# mcu_atmega.net
KiCad netlist of a schematic drawn in Altium Designer
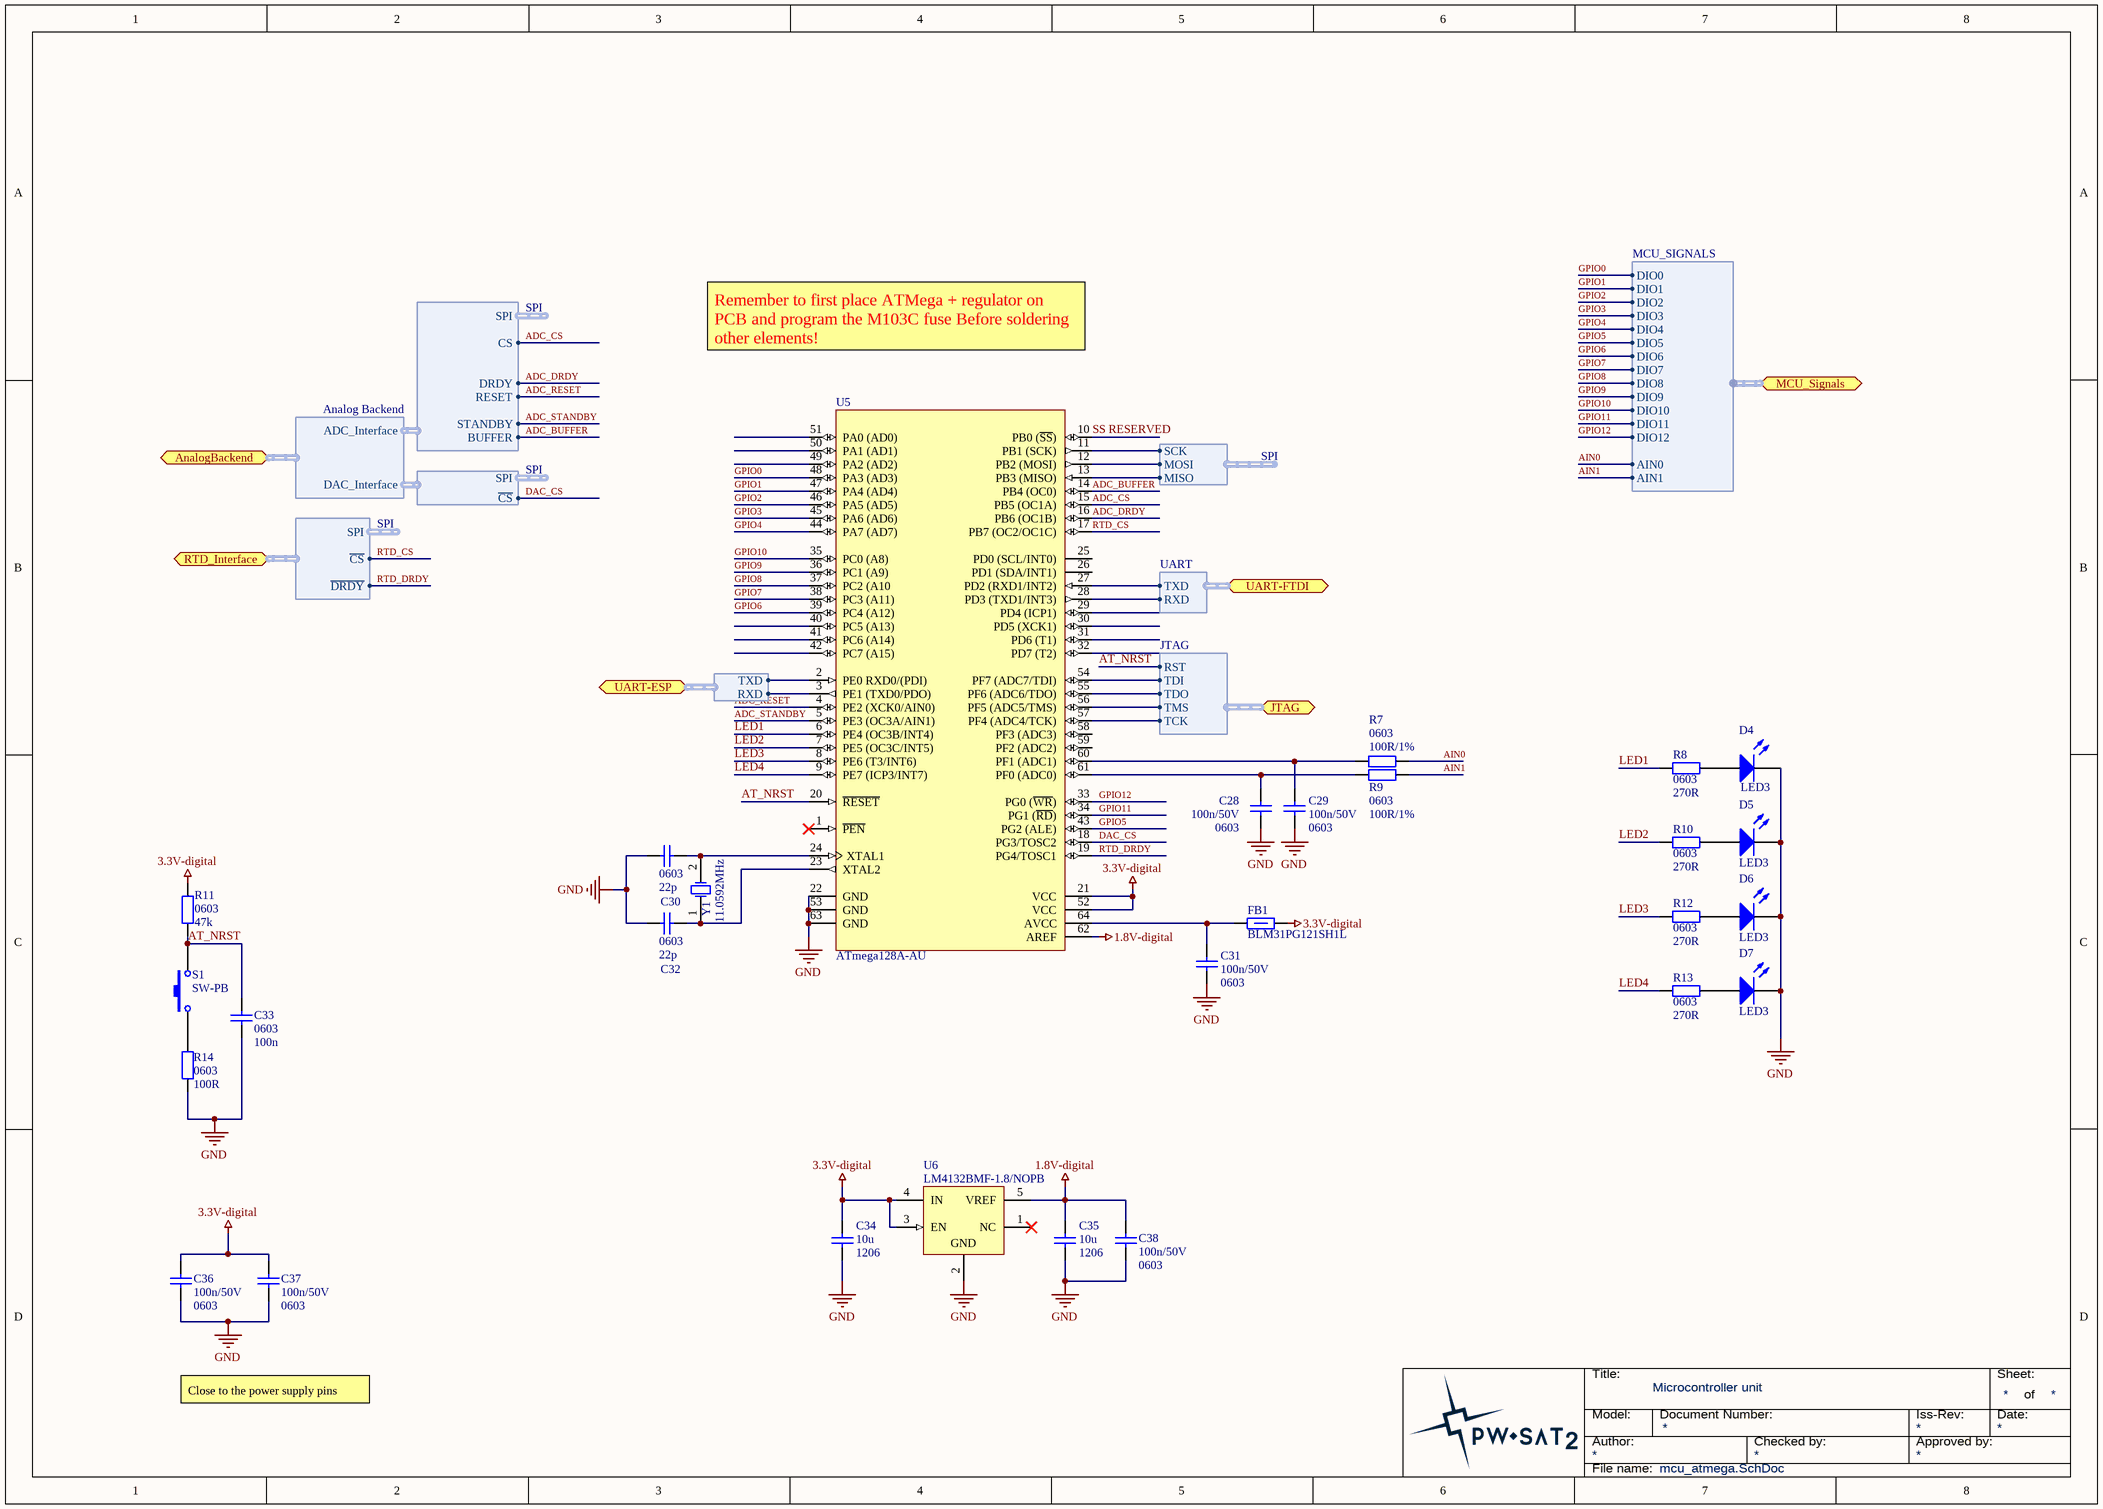
[diagram p0: mcu_atmega.SchDoc]

(export (version "E")
  (design (tool "Eeschema 10.0.6"))
  (components
    (comp (ref "C28")
      (value "100n/50V")
      (footprint "SMD_Capacitor_0603")
      (description "Ceramic Cap Kemet COTS 100n/50V X7R 0603")
      (fields
        (field (name "MANUFACTURER") "Kemet")
        (field (name "MANUFACTURERPARTNUMBER") "C0603T104K5RALTU")
        (field (name "PACKAGE") "0603")
      )
      (libsource (lib "capacitors") (part "Cer_C0603T104K5RALTU"))
    )
    (comp (ref "C29")
      (value "100n/50V")
      (footprint "SMD_Capacitor_0603")
      (description "Ceramic Cap Kemet COTS 100n/50V X7R 0603")
      (fields
        (field (name "MANUFACTURER") "Kemet")
        (field (name "MANUFACTURERPARTNUMBER") "C0603T104K5RALTU")
        (field (name "PACKAGE") "0603")
      )
      (libsource (lib "capacitors") (part "Cer_C0603T104K5RALTU"))
    )
    (comp (ref "C30")
      (value "0603")
      (footprint "SMD_Capacitor_0603")
      (description "Capacitor")
      (fields (field (name "ALTIUM_VALUE") "22p") (field (name "PUBLISHER") "Altium Limited"))
      (libsource (lib "Miscellaneous Devices") (part "Cap"))
    )
    (comp (ref "C31")
      (value "100n/50V")
      (footprint "SMD_Capacitor_0603")
      (description "Ceramic Cap Kemet COTS 100n/50V X7R 0603")
      (fields
        (field (name "MANUFACTURER") "Kemet")
        (field (name "MANUFACTURERPARTNUMBER") "C0603T104K5RALTU")
        (field (name "PACKAGE") "0603")
      )
      (libsource (lib "capacitors") (part "Cer_C0603T104K5RALTU"))
    )
    (comp (ref "C32")
      (value "0603")
      (footprint "SMD_Capacitor_0603")
      (description "Capacitor")
      (fields (field (name "ALTIUM_VALUE") "22p") (field (name "PUBLISHER") "Altium Limited"))
      (libsource (lib "Miscellaneous Devices") (part "Cap"))
    )
    (comp (ref "C33")
      (value "0603")
      (footprint "SMD_Capacitor_0603")
      (description "Capacitor")
      (fields (field (name "ALTIUM_VALUE") "100n") (field (name "PUBLISHER") "Altium Limited"))
      (libsource (lib "Miscellaneous Devices") (part "Cap"))
    )
    (comp (ref "C34")
      (value "10u")
      (footprint "SMD_Capacitor_1206")
      (description "Cap")
      (fields (field (name "PACKAGE") "1206"))
      (libsource (lib "capacitors") (part "Cap"))
    )
    (comp (ref "C35")
      (value "10u")
      (footprint "SMD_Capacitor_1206")
      (description "Cap")
      (fields (field (name "PACKAGE") "1206"))
      (libsource (lib "capacitors") (part "Cap"))
    )
    (comp (ref "C36")
      (value "100n/50V")
      (footprint "SMD_Capacitor_0603")
      (description "Ceramic Cap Kemet COTS 100n/50V X7R 0603")
      (fields
        (field (name "MANUFACTURER") "Kemet")
        (field (name "MANUFACTURERPARTNUMBER") "C0603T104K5RALTU")
        (field (name "PACKAGE") "0603")
      )
      (libsource (lib "capacitors") (part "Cer_C0603T104K5RALTU"))
    )
    (comp (ref "C37")
      (value "100n/50V")
      (footprint "SMD_Capacitor_0603")
      (description "Ceramic Cap Kemet COTS 100n/50V X7R 0603")
      (fields
        (field (name "MANUFACTURER") "Kemet")
        (field (name "MANUFACTURERPARTNUMBER") "C0603T104K5RALTU")
        (field (name "PACKAGE") "0603")
      )
      (libsource (lib "capacitors") (part "Cer_C0603T104K5RALTU"))
    )
    (comp (ref "C38")
      (value "100n/50V")
      (footprint "SMD_Capacitor_0603")
      (description "Ceramic Cap Kemet COTS 100n/50V X7R 0603")
      (fields
        (field (name "MANUFACTURER") "Kemet")
        (field (name "MANUFACTURERPARTNUMBER") "C0603T104K5RALTU")
        (field (name "PACKAGE") "0603")
      )
      (libsource (lib "capacitors") (part "Cer_C0603T104K5RALTU"))
    )
    (comp (ref "D4")
      (value "LED3")
      (footprint "LED 0805 Blue")
      (description "Typical BLUE SiC LED")
      (fields (field (name "PUBLISHER") "Altium Limited"))
      (libsource (lib "Miscellaneous Devices") (part "LED3"))
    )
    (comp (ref "D5")
      (value "LED3")
      (footprint "LED 0805 Yellow")
      (description "Typical BLUE SiC LED")
      (fields (field (name "PUBLISHER") "Altium Limited"))
      (libsource (lib "Miscellaneous Devices") (part "LED3"))
    )
    (comp (ref "D6")
      (value "LED3")
      (footprint "LED 0805 GREEN")
      (description "Typical BLUE SiC LED")
      (fields (field (name "PUBLISHER") "Altium Limited"))
      (libsource (lib "Miscellaneous Devices") (part "LED3"))
    )
    (comp (ref "D7")
      (value "LED3")
      (footprint "LED 0805 RED")
      (description "Typical BLUE SiC LED")
      (fields (field (name "PUBLISHER") "Altium Limited"))
      (libsource (lib "Miscellaneous Devices") (part "LED3"))
    )
    (comp (ref "FB1")
      (value "120R/100MHz")
      (footprint "SMD_FerriteBead_1206")
      (description "Ferrite bead, 1206, 0.02HM, 3.5A.")
      (fields (field (name "MANUFACTURER") "Murata") (field (name "MANUFACTURERPARTNUMBER") "BLM31PG121SH1L"))
      (libsource (lib "inductors") (part "BLM31PG121SH1L"))
    )
    (comp (ref "R7")
      (value "100R/1%")
      (footprint "SMD_Resistor_0603")
      (description "100R/1% Vishay CRCW 0603 Resistor. 100mW, 100ppm, 75V.")
      (fields
        (field (name "MANUFACTURER") "Vishay")
        (field (name "MANUFACTURERPARTNUMBER") "CRCW0603100RFKxxxx")
        (field (name "PACKAGE") "0603")
      )
      (libsource (lib "resistors") (part "CRCW0603100RFKxxxx"))
    )
    (comp (ref "R8")
      (value "0603")
      (footprint "SMD_Resistor_0603")
      (description "Resistor")
      (fields (field (name "ALTIUM_VALUE") "270R") (field (name "PUBLISHER") "Altium Limited"))
      (libsource (lib "Miscellaneous Devices") (part "Res2"))
    )
    (comp (ref "R9")
      (value "100R/1%")
      (footprint "SMD_Resistor_0603")
      (description "100R/1% Vishay CRCW 0603 Resistor. 100mW, 100ppm, 75V.")
      (fields
        (field (name "MANUFACTURER") "Vishay")
        (field (name "MANUFACTURERPARTNUMBER") "CRCW0603100RFKxxxx")
        (field (name "PACKAGE") "0603")
      )
      (libsource (lib "") (part "CRCW0603100RFKxxxx_1"))
    )
    (comp (ref "R10")
      (value "0603")
      (footprint "SMD_Resistor_0603")
      (description "Resistor")
      (fields (field (name "ALTIUM_VALUE") "270R") (field (name "PUBLISHER") "Altium Limited"))
      (libsource (lib "Miscellaneous Devices") (part "Res2"))
    )
    (comp (ref "R11")
      (value "0603")
      (footprint "SMD_Resistor_0603")
      (description "Resistor")
      (fields (field (name "ALTIUM_VALUE") "47k") (field (name "PUBLISHER") "Altium Limited"))
      (libsource (lib "") (part "Res2_2"))
    )
    (comp (ref "R12")
      (value "0603")
      (footprint "SMD_Resistor_0603")
      (description "Resistor")
      (fields (field (name "ALTIUM_VALUE") "270R") (field (name "PUBLISHER") "Altium Limited"))
      (libsource (lib "Miscellaneous Devices") (part "Res2"))
    )
    (comp (ref "R13")
      (value "0603")
      (footprint "SMD_Resistor_0603")
      (description "Resistor")
      (fields (field (name "ALTIUM_VALUE") "270R") (field (name "PUBLISHER") "Altium Limited"))
      (libsource (lib "Miscellaneous Devices") (part "Res2"))
    )
    (comp (ref "R14")
      (value "0603")
      (footprint "SMD_Resistor_0603")
      (description "Resistor")
      (fields (field (name "ALTIUM_VALUE") "100R") (field (name "PUBLISHER") "Altium Limited"))
      (libsource (lib "") (part "Res2_1"))
    )
    (comp (ref "S1")
      (value "SW-PB")
      (footprint "Tact Switch 3x6")
      (description "Switch")
      (fields (field (name "PUBLISHER") "Altium Limited"))
      (libsource (lib "Miscellaneous Devices") (part "SW-PB"))
    )
    (comp (ref "U5")
      (value "ATmega128A-AU")
      (footprint "64A_M")
      (libsource (lib "Atmel Microcontroller megaAVR") (part "ATmega128A-AU"))
    )
    (comp (ref "U6")
      (value "LM4132BMF-1.8/NOPB")
      (footprint "MF05A_N")
      (description "Precision Low Dropout Voltage Reference, 5-pin SOT-23, Pb-Free")
      (fields (field (name "MANUFACTURER") "National Semiconductor"))
      (libsource (lib "National Semiconductor Voltage Reference") (part "LM4132BMF-1.8/NOPB"))
    )
    (comp (ref "Y1")
      (value "11.0592MHz")
      (footprint "CRYSTAL_HC49-US-SM")
      (description "LF XTAL003519")
      (fields (field (name "PUBLISHER") "Altium Limited"))
      (libsource (lib "Miscellaneous Devices") (part "XTAL"))
    )
  )
  (nets
    (net (code "11") (name "/ADC_BUFFER") (class "Default")
      (node (ref "U5") (pin "14") (pinfunction "PB4_(OC0)_14") (pintype "bidirectional"))
    )
    (net (code "12") (name "/ADC_CS") (class "Default")
      (node (ref "U5") (pin "15") (pinfunction "PB5_(OC1A)_15") (pintype "bidirectional"))
    )
    (net (code "13") (name "/ADC_DRDY") (class "Default")
      (node (ref "U5") (pin "16") (pinfunction "PB6_(OC1B)_16") (pintype "bidirectional"))
    )
    (net (code "14") (name "/ADC_RESET") (class "Default")
      (node (ref "U5") (pin "4") (pinfunction "PE2_(XCK0/AIN0)_4") (pintype "bidirectional"))
    )
    (net (code "15") (name "/ADC_STANDBY") (class "Default")
      (node (ref "U5") (pin "5") (pinfunction "PE3_(OC3A/AIN1)_5") (pintype "bidirectional"))
    )
    (net (code "16") (name "/AIN0") (class "Default")
      (node (ref "R7") (pin "1") (pinfunction "1_1") (pintype "passive"))
    )
    (net (code "17") (name "/AIN1") (class "Default")
      (node (ref "R9") (pin "2") (pinfunction "2_2") (pintype "passive"))
    )
    (net (code "18") (name "/AT_NRST") (class "Default")
      (node (ref "C33") (pin "2") (pinfunction "2_2") (pintype "passive"))
      (node (ref "R11") (pin "1") (pinfunction "1_1") (pintype "passive"))
      (node (ref "S1") (pin "2") (pinfunction "2_2") (pintype "passive"))
      (node (ref "U5") (pin "20") (pinfunction "~{RESET}_20") (pintype "input"))
    )
    (net (code "19") (name "/DAC_CS") (class "Default")
      (node (ref "U5") (pin "18") (pinfunction "PG3/TOSC2_18") (pintype "bidirectional"))
    )
    (net (code "20") (name "/GPIO0") (class "Default")
      (node (ref "U5") (pin "48") (pinfunction "PA3_(AD3)_48") (pintype "bidirectional"))
    )
    (net (code "21") (name "/GPIO1") (class "Default")
      (node (ref "U5") (pin "47") (pinfunction "PA4_(AD4)_47") (pintype "bidirectional"))
    )
    (net (code "22") (name "/GPIO2") (class "Default")
      (node (ref "U5") (pin "46") (pinfunction "PA5_(AD5)_46") (pintype "bidirectional"))
    )
    (net (code "23") (name "/GPIO3") (class "Default")
      (node (ref "U5") (pin "45") (pinfunction "PA6_(AD6)_45") (pintype "bidirectional"))
    )
    (net (code "24") (name "/GPIO4") (class "Default")
      (node (ref "U5") (pin "44") (pinfunction "PA7_(AD7)_44") (pintype "bidirectional"))
    )
    (net (code "25") (name "/GPIO5") (class "Default")
      (node (ref "U5") (pin "43") (pinfunction "PG2_(ALE)_43") (pintype "bidirectional"))
    )
    (net (code "26") (name "/GPIO6") (class "Default")
      (node (ref "U5") (pin "39") (pinfunction "PC4_(A12)_39") (pintype "bidirectional"))
    )
    (net (code "27") (name "/GPIO7") (class "Default")
      (node (ref "U5") (pin "38") (pinfunction "PC3_(A11)_38") (pintype "bidirectional"))
    )
    (net (code "28") (name "/GPIO8") (class "Default")
      (node (ref "U5") (pin "37") (pinfunction "PC2_(A10_37") (pintype "bidirectional"))
    )
    (net (code "29") (name "/GPIO9") (class "Default")
      (node (ref "U5") (pin "36") (pinfunction "PC1_(A9)_36") (pintype "bidirectional"))
    )
    (net (code "30") (name "/GPIO10") (class "Default")
      (node (ref "U5") (pin "35") (pinfunction "PC0_(A8)_35") (pintype "bidirectional"))
    )
    (net (code "31") (name "/GPIO11") (class "Default")
      (node (ref "U5") (pin "34") (pinfunction "PG1_(~{RD})_34") (pintype "bidirectional"))
    )
    (net (code "32") (name "/GPIO12") (class "Default")
      (node (ref "U5") (pin "33") (pinfunction "PG0_(~{WR})_33") (pintype "bidirectional"))
    )
    (net (code "33") (name "/LED1") (class "Default")
      (node (ref "R8") (pin "2") (pinfunction "2_2") (pintype "passive"))
      (node (ref "U5") (pin "6") (pinfunction "PE4_(OC3B/INT4)_6") (pintype "bidirectional"))
    )
    (net (code "34") (name "/LED2") (class "Default")
      (node (ref "R10") (pin "2") (pinfunction "2_2") (pintype "passive"))
      (node (ref "U5") (pin "7") (pinfunction "PE5_(OC3C/INT5)_7") (pintype "bidirectional"))
    )
    (net (code "35") (name "/LED3") (class "Default")
      (node (ref "R12") (pin "2") (pinfunction "2_2") (pintype "passive"))
      (node (ref "U5") (pin "8") (pinfunction "PE6_(T3/INT6)_8") (pintype "bidirectional"))
    )
    (net (code "36") (name "/LED4") (class "Default")
      (node (ref "R13") (pin "2") (pinfunction "2_2") (pintype "passive"))
      (node (ref "U5") (pin "9") (pinfunction "PE7_(ICP3/INT7)_9") (pintype "bidirectional"))
    )
    (net (code "37") (name "/MISO") (class "Default")
      (node (ref "U5") (pin "13") (pinfunction "PB3_(MISO)_13") (pintype "input"))
    )
    (net (code "38") (name "/MOSI") (class "Default")
      (node (ref "U5") (pin "12") (pinfunction "PB2_(MOSI)_12") (pintype "output"))
    )
    (net (code "39") (name "/RTD_CS") (class "Default")
      (node (ref "U5") (pin "17") (pinfunction "PB7_(OC2/OC1C)_17") (pintype "bidirectional"))
    )
    (net (code "40") (name "/RTD_DRDY") (class "Default")
      (node (ref "U5") (pin "19") (pinfunction "PG4/TOSC1_19") (pintype "bidirectional"))
    )
    (net (code "42") (name "/SCK") (class "Default")
      (node (ref "U5") (pin "11") (pinfunction "PB1_(SCK)_11") (pintype "output"))
    )
    (net (code "47") (name "/SS RESERVED") (class "Default")
      (node (ref "U5") (pin "10") (pinfunction "PB0_(~{SS})_10") (pintype "bidirectional"))
    )
    (net (code "48") (name "/TCK") (class "Default")
      (node (ref "U5") (pin "57") (pinfunction "PF4_(ADC4/TCK)_57") (pintype "bidirectional"))
    )
    (net (code "49") (name "/TDI") (class "Default")
      (node (ref "U5") (pin "54") (pinfunction "PF7_(ADC7/TDI)_54") (pintype "bidirectional"))
    )
    (net (code "50") (name "/TDO") (class "Default")
      (node (ref "U5") (pin "55") (pinfunction "PF6_(ADC6/TDO)_55") (pintype "bidirectional"))
    )
    (net (code "51") (name "/TMS") (class "Default")
      (node (ref "U5") (pin "56") (pinfunction "PF5_(ADC5/TMS)_56") (pintype "bidirectional"))
    )
    (net (code "56") (name "1.8V-digital") (class "Default")
      (node (ref "C35") (pin "1") (pinfunction "1_1") (pintype "passive"))
      (node (ref "C38") (pin "1") (pinfunction "1_1") (pintype "passive"))
      (node (ref "U5") (pin "62") (pinfunction "AREF_62") (pintype "power_in"))
      (node (ref "U6") (pin "5") (pinfunction "VREF_5") (pintype "power_in"))
    )
    (net (code "57") (name "3.3V-digital") (class "Default")
      (node (ref "C34") (pin "1") (pinfunction "1_1") (pintype "passive"))
      (node (ref "C36") (pin "1") (pinfunction "1_1") (pintype "passive"))
      (node (ref "C37") (pin "1") (pinfunction "1_1") (pintype "passive"))
      (node (ref "FB1") (pin "1") (pinfunction "1_1") (pintype "passive"))
      (node (ref "R11") (pin "2") (pinfunction "2_2") (pintype "passive"))
      (node (ref "U5") (pin "21") (pinfunction "VCC_21") (pintype "power_in"))
      (node (ref "U5") (pin "52") (pinfunction "VCC_52") (pintype "power_in"))
      (node (ref "U6") (pin "3") (pinfunction "EN_3") (pintype "input"))
      (node (ref "U6") (pin "4") (pinfunction "IN_4") (pintype "power_in"))
    )
    (net (code "58") (name "GND") (class "Default")
      (node (ref "C28") (pin "2") (pinfunction "2_2") (pintype "passive"))
      (node (ref "C29") (pin "2") (pinfunction "2_2") (pintype "passive"))
      (node (ref "C30") (pin "1") (pinfunction "1_1") (pintype "passive"))
      (node (ref "C31") (pin "2") (pinfunction "2_2") (pintype "passive"))
      (node (ref "C32") (pin "1") (pinfunction "1_1") (pintype "passive"))
      (node (ref "C33") (pin "1") (pinfunction "1_1") (pintype "passive"))
      (node (ref "C34") (pin "2") (pinfunction "2_2") (pintype "passive"))
      (node (ref "C35") (pin "2") (pinfunction "2_2") (pintype "passive"))
      (node (ref "C36") (pin "2") (pinfunction "2_2") (pintype "passive"))
      (node (ref "C37") (pin "2") (pinfunction "2_2") (pintype "passive"))
      (node (ref "C38") (pin "2") (pinfunction "2_2") (pintype "passive"))
      (node (ref "D4") (pin "2") (pinfunction "K_2") (pintype "passive"))
      (node (ref "D5") (pin "2") (pinfunction "K_2") (pintype "passive"))
      (node (ref "D6") (pin "2") (pinfunction "K_2") (pintype "passive"))
      (node (ref "D7") (pin "2") (pinfunction "K_2") (pintype "passive"))
      (node (ref "R14") (pin "2") (pinfunction "2_2") (pintype "passive"))
      (node (ref "U5") (pin "22") (pinfunction "GND_22") (pintype "power_in"))
      (node (ref "U5") (pin "53") (pinfunction "GND_53") (pintype "power_in"))
      (node (ref "U5") (pin "63") (pinfunction "GND_63") (pintype "power_in"))
      (node (ref "U6") (pin "2") (pinfunction "GND_2") (pintype "power_in"))
    )
    (net (code "59") (name "Net-(D4-A)") (class "Default")
      (node (ref "D4") (pin "1") (pinfunction "A_1") (pintype "passive"))
      (node (ref "R8") (pin "1") (pinfunction "1_1") (pintype "passive"))
    )
    (net (code "60") (name "Net-(D5-A)") (class "Default")
      (node (ref "D5") (pin "1") (pinfunction "A_1") (pintype "passive"))
      (node (ref "R10") (pin "1") (pinfunction "1_1") (pintype "passive"))
    )
    (net (code "61") (name "Net-(D6-A)") (class "Default")
      (node (ref "D6") (pin "1") (pinfunction "A_1") (pintype "passive"))
      (node (ref "R12") (pin "1") (pinfunction "1_1") (pintype "passive"))
    )
    (net (code "62") (name "Net-(D7-A)") (class "Default")
      (node (ref "D7") (pin "1") (pinfunction "A_1") (pintype "passive"))
      (node (ref "R13") (pin "1") (pinfunction "1_1") (pintype "passive"))
    )
    (net (code "63") (name "Net-(R14-Pad1)") (class "Default")
      (node (ref "R14") (pin "1") (pinfunction "1_1") (pintype "passive"))
      (node (ref "S1") (pin "1") (pinfunction "1_1") (pintype "passive"))
    )
    (net (code "64") (name "Net-(U5-AVCC)") (class "Default")
      (node (ref "C31") (pin "1") (pinfunction "1_1") (pintype "passive"))
      (node (ref "FB1") (pin "2") (pinfunction "2_2") (pintype "passive"))
      (node (ref "U5") (pin "64") (pinfunction "AVCC_64") (pintype "power_in"))
    )
    (net (code "65") (name "Net-(U5-PF0_(ADC0))") (class "Default")
      (node (ref "C28") (pin "1") (pinfunction "1_1") (pintype "passive"))
      (node (ref "R9") (pin "1") (pinfunction "1_1") (pintype "passive"))
      (node (ref "U5") (pin "61") (pinfunction "PF0_(ADC0)_61") (pintype "bidirectional"))
    )
    (net (code "66") (name "Net-(U5-PF1_(ADC1))") (class "Default")
      (node (ref "C29") (pin "1") (pinfunction "1_1") (pintype "passive"))
      (node (ref "R7") (pin "2") (pinfunction "2_2") (pintype "passive"))
      (node (ref "U5") (pin "60") (pinfunction "PF1_(ADC1)_60") (pintype "bidirectional"))
    )
    (net (code "67") (name "Net-(U5-XTAL1)") (class "Default")
      (node (ref "C30") (pin "2") (pinfunction "2_2") (pintype "passive"))
      (node (ref "U5") (pin "24") (pinfunction "XTAL1_24") (pintype "input"))
      (node (ref "Y1") (pin "2") (pinfunction "OSC2_2") (pintype "passive"))
    )
    (net (code "68") (name "Net-(U5-XTAL2)") (class "Default")
      (node (ref "C32") (pin "2") (pinfunction "2_2") (pintype "passive"))
      (node (ref "U5") (pin "23") (pinfunction "XTAL2_23") (pintype "output"))
      (node (ref "Y1") (pin "1") (pinfunction "OSC1_1") (pintype "passive"))
    )
    (net (code "69") (name "unconnected-(U5-PA0_(AD0)-Pad51)") (class "Default")
      (node (ref "U5") (pin "51") (pinfunction "PA0_(AD0)_51") (pintype "bidirectional"))
    )
    (net (code "70") (name "unconnected-(U5-PA1_(AD1)-Pad50)") (class "Default")
      (node (ref "U5") (pin "50") (pinfunction "PA1_(AD1)_50") (pintype "bidirectional"))
    )
    (net (code "71") (name "unconnected-(U5-PA2_(AD2)-Pad49)") (class "Default")
      (node (ref "U5") (pin "49") (pinfunction "PA2_(AD2)_49") (pintype "bidirectional"))
    )
    (net (code "72") (name "unconnected-(U5-PC5_(A13)-Pad40)") (class "Default")
      (node (ref "U5") (pin "40") (pinfunction "PC5_(A13)_40") (pintype "bidirectional"))
    )
    (net (code "73") (name "unconnected-(U5-PC6_(A14)-Pad41)") (class "Default")
      (node (ref "U5") (pin "41") (pinfunction "PC6_(A14)_41") (pintype "bidirectional"))
    )
    (net (code "74") (name "unconnected-(U5-PC7_(A15)-Pad42)") (class "Default")
      (node (ref "U5") (pin "42") (pinfunction "PC7_(A15)_42") (pintype "bidirectional"))
    )
    (net (code "75") (name "unconnected-(U5-PD0_(SCL{slash}INT0)-Pad25)") (class "Default")
      (node (ref "U5") (pin "25") (pinfunction "PD0_(SCL/INT0)_25") (pintype "open_collector"))
    )
    (net (code "76") (name "unconnected-(U5-PD1_(SDA{slash}INT1)-Pad26)") (class "Default")
      (node (ref "U5") (pin "26") (pinfunction "PD1_(SDA/INT1)_26") (pintype "open_collector"))
    )
    (net (code "77") (name "unconnected-(U5-PD2_(RXD1{slash}INT2)-Pad27)") (class "Default")
      (node (ref "U5") (pin "27") (pinfunction "PD2_(RXD1/INT2)_27") (pintype "input"))
    )
    (net (code "78") (name "unconnected-(U5-PD3_(TXD1{slash}INT3)-Pad28)") (class "Default")
      (node (ref "U5") (pin "28") (pinfunction "PD3_(TXD1/INT3)_28") (pintype "output"))
    )
    (net (code "79") (name "unconnected-(U5-PD4_(ICP1)-Pad29)") (class "Default")
      (node (ref "U5") (pin "29") (pinfunction "PD4_(ICP1)_29") (pintype "bidirectional"))
    )
    (net (code "80") (name "unconnected-(U5-PD5_(XCK1)-Pad30)") (class "Default")
      (node (ref "U5") (pin "30") (pinfunction "PD5_(XCK1)_30") (pintype "bidirectional"))
    )
    (net (code "81") (name "unconnected-(U5-PD6_(T1)-Pad31)") (class "Default")
      (node (ref "U5") (pin "31") (pinfunction "PD6_(T1)_31") (pintype "bidirectional"))
    )
    (net (code "82") (name "unconnected-(U5-PD7_(T2)-Pad32)") (class "Default")
      (node (ref "U5") (pin "32") (pinfunction "PD7_(T2)_32") (pintype "bidirectional"))
    )
    (net (code "83") (name "unconnected-(U5-PE0_RXD0{slash}(PDI)-Pad2)") (class "Default")
      (node (ref "U5") (pin "2") (pinfunction "PE0_RXD0/(PDI)_2") (pintype "input"))
    )
    (net (code "84") (name "unconnected-(U5-PE1_(TXD0{slash}PDO)-Pad3)") (class "Default")
      (node (ref "U5") (pin "3") (pinfunction "PE1_(TXD0/PDO)_3") (pintype "output"))
    )
    (net (code "85") (name "unconnected-(U5-PF2_(ADC2)-Pad59)") (class "Default")
      (node (ref "U5") (pin "59") (pinfunction "PF2_(ADC2)_59") (pintype "bidirectional"))
    )
    (net (code "86") (name "unconnected-(U5-PF3_(ADC3)-Pad58)") (class "Default")
      (node (ref "U5") (pin "58") (pinfunction "PF3_(ADC3)_58") (pintype "bidirectional"))
    )
    (net (code "87") (name "unconnected-(U5-~{PEN}-Pad1)") (class "Default")
      (node (ref "U5") (pin "1") (pinfunction "~{PEN}_1") (pintype "input+no_connect"))
    )
    (net (code "88") (name "unconnected-(U6-NC-Pad1)") (class "Default")
      (node (ref "U6") (pin "1") (pinfunction "NC_1") (pintype "passive+no_connect"))
    )
  )
)
